# Tactile_Sensing_Module_Orientation_4.net
KiCad netlist of a schematic drawn in EAGLE
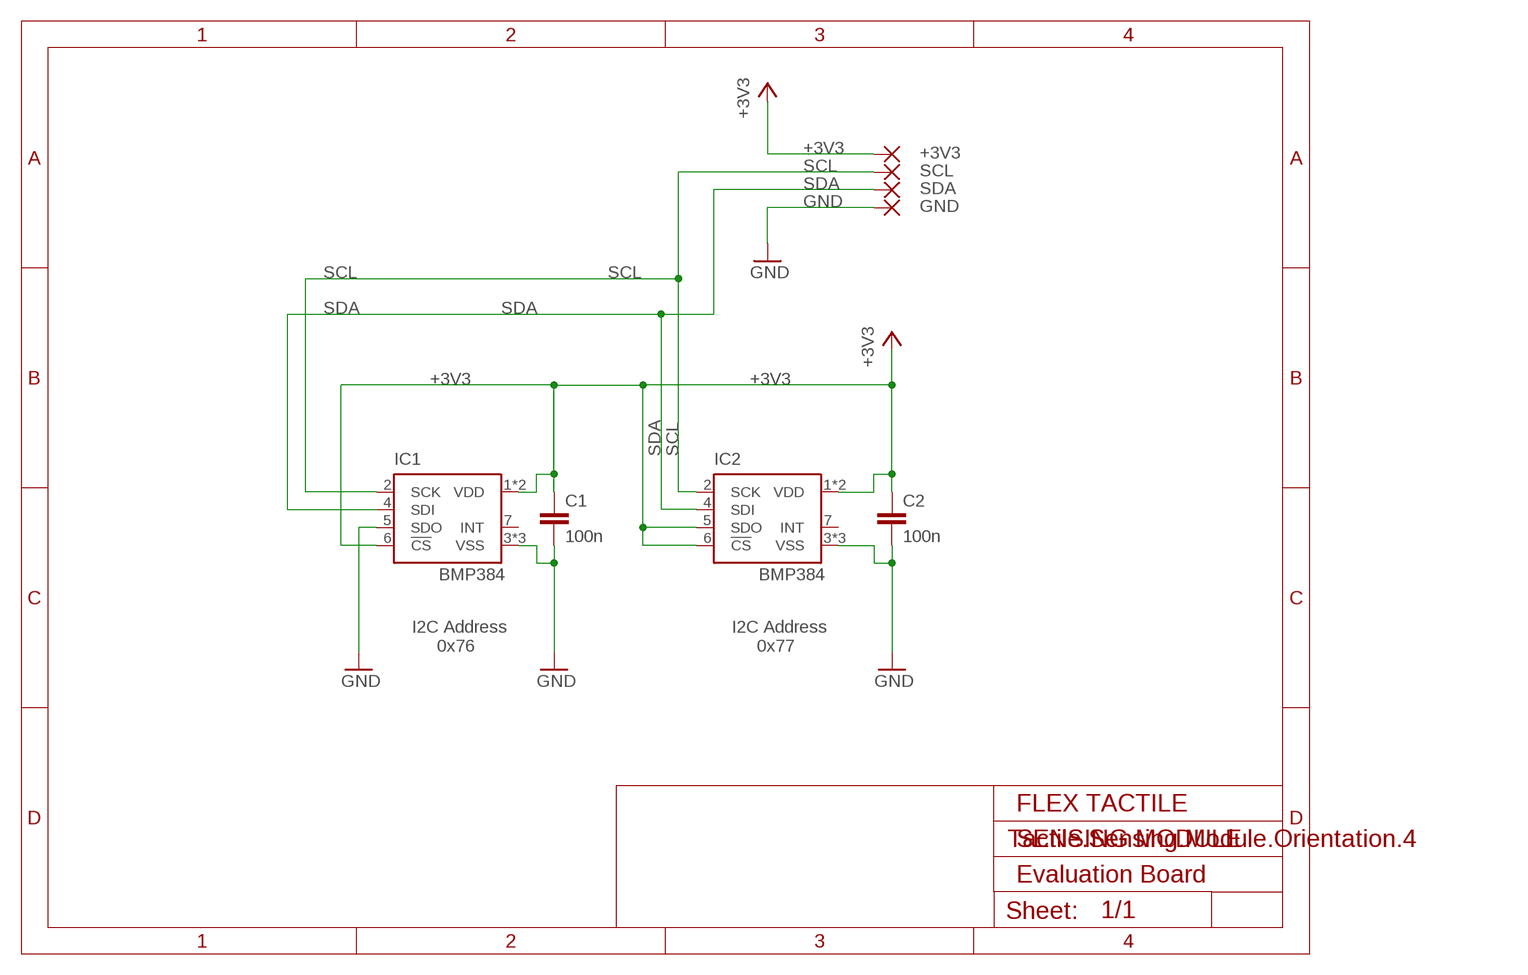
[diagram p0: schematic, sheet 1]

(export (version "E")
  (design (tool "Eeschema 10.0.6"))
  (components
    (comp (ref "+3V3")
      (value "SMD-PAD-2MMX4MM")
      (footprint "eagle-import:SMD-PAD-2MMX4MM")
      (libsource (lib "eagle-import") (part "SMD-PAD-2MMX4MM"))
    )
    (comp (ref "C1")
      (value "100n")
      (footprint "eagle-import:C0201")
      (libsource (lib "eagle-import") (part "C-EUC0201"))
    )
    (comp (ref "C2")
      (value "100n")
      (footprint "eagle-import:C0201")
      (libsource (lib "eagle-import") (part "C-EUC0201"))
    )
    (comp (ref "GND")
      (value "SMD-PAD-2MMX4MM")
      (footprint "eagle-import:SMD-PAD-2MMX4MM")
      (libsource (lib "eagle-import") (part "SMD-PAD-2MMX4MM"))
    )
    (comp (ref "IC1")
      (value "BMP384")
      (footprint "eagle-import:BMP384")
      (libsource (lib "eagle-import") (part "BMP384"))
    )
    (comp (ref "IC2")
      (value "BMP384")
      (footprint "eagle-import:BMP384")
      (libsource (lib "eagle-import") (part "BMP384"))
    )
    (comp (ref "SCL")
      (value "SMD-PAD-2MMX4MM")
      (footprint "eagle-import:SMD-PAD-2MMX4MM")
      (libsource (lib "eagle-import") (part "SMD-PAD-2MMX4MM"))
    )
    (comp (ref "SDA")
      (value "SMD-PAD-2MMX4MM")
      (footprint "eagle-import:SMD-PAD-2MMX4MM")
      (libsource (lib "eagle-import") (part "SMD-PAD-2MMX4MM"))
    )
  )
  (nets
    (net (code "1") (name "+3V3") (class "Default")
      (node (ref "+3V3") (pin "1") (pinfunction "P_1") (pintype "bidirectional"))
      (node (ref "C1") (pin "1") (pinfunction "1_1") (pintype "passive"))
      (node (ref "C2") (pin "1") (pinfunction "1_1") (pintype "passive"))
      (node (ref "IC1") (pin "1") (pinfunction "VDD_1") (pintype "bidirectional"))
      (node (ref "IC1") (pin "10") (pinfunction "VDD_10") (pintype "bidirectional"))
      (node (ref "IC1") (pin "6") (pinfunction "~{CS}_6") (pintype "bidirectional"))
      (node (ref "IC2") (pin "1") (pinfunction "VDD_1") (pintype "bidirectional"))
      (node (ref "IC2") (pin "10") (pinfunction "VDD_10") (pintype "bidirectional"))
      (node (ref "IC2") (pin "5") (pinfunction "SDO_5") (pintype "bidirectional"))
      (node (ref "IC2") (pin "6") (pinfunction "~{CS}_6") (pintype "bidirectional"))
    )
    (net (code "2") (name "/SCL") (class "Default")
      (node (ref "IC1") (pin "2") (pinfunction "SCK_2") (pintype "input"))
      (node (ref "IC2") (pin "2") (pinfunction "SCK_2") (pintype "input"))
      (node (ref "SCL") (pin "1") (pinfunction "P_1") (pintype "bidirectional"))
    )
    (net (code "3") (name "/SDA") (class "Default")
      (node (ref "IC1") (pin "4") (pinfunction "SDI_4") (pintype "bidirectional"))
      (node (ref "IC2") (pin "4") (pinfunction "SDI_4") (pintype "bidirectional"))
      (node (ref "SDA") (pin "1") (pinfunction "P_1") (pintype "bidirectional"))
    )
    (net (code "4") (name "GND") (class "Default")
      (node (ref "C1") (pin "2") (pinfunction "2_2") (pintype "passive"))
      (node (ref "C2") (pin "2") (pinfunction "2_2") (pintype "passive"))
      (node (ref "GND") (pin "1") (pinfunction "P_1") (pintype "bidirectional"))
      (node (ref "IC1") (pin "3") (pinfunction "VSS_3") (pintype "bidirectional"))
      (node (ref "IC1") (pin "5") (pinfunction "SDO_5") (pintype "bidirectional"))
      (node (ref "IC1") (pin "8") (pinfunction "VSS_8") (pintype "bidirectional"))
      (node (ref "IC1") (pin "9") (pinfunction "VSS_9") (pintype "bidirectional"))
      (node (ref "IC2") (pin "3") (pinfunction "VSS_3") (pintype "bidirectional"))
      (node (ref "IC2") (pin "8") (pinfunction "VSS_8") (pintype "bidirectional"))
      (node (ref "IC2") (pin "9") (pinfunction "VSS_9") (pintype "bidirectional"))
    )
    (net (code "5") (name "unconnected-(IC1-INT-Pad7)") (class "Default")
      (node (ref "IC1") (pin "7") (pinfunction "INT_7") (pintype "output"))
    )
    (net (code "6") (name "unconnected-(IC2-INT-Pad7)") (class "Default")
      (node (ref "IC2") (pin "7") (pinfunction "INT_7") (pintype "output"))
    )
  )
)
